# mega_shield_despair.net
KiCad netlist of a schematic drawn in EAGLE
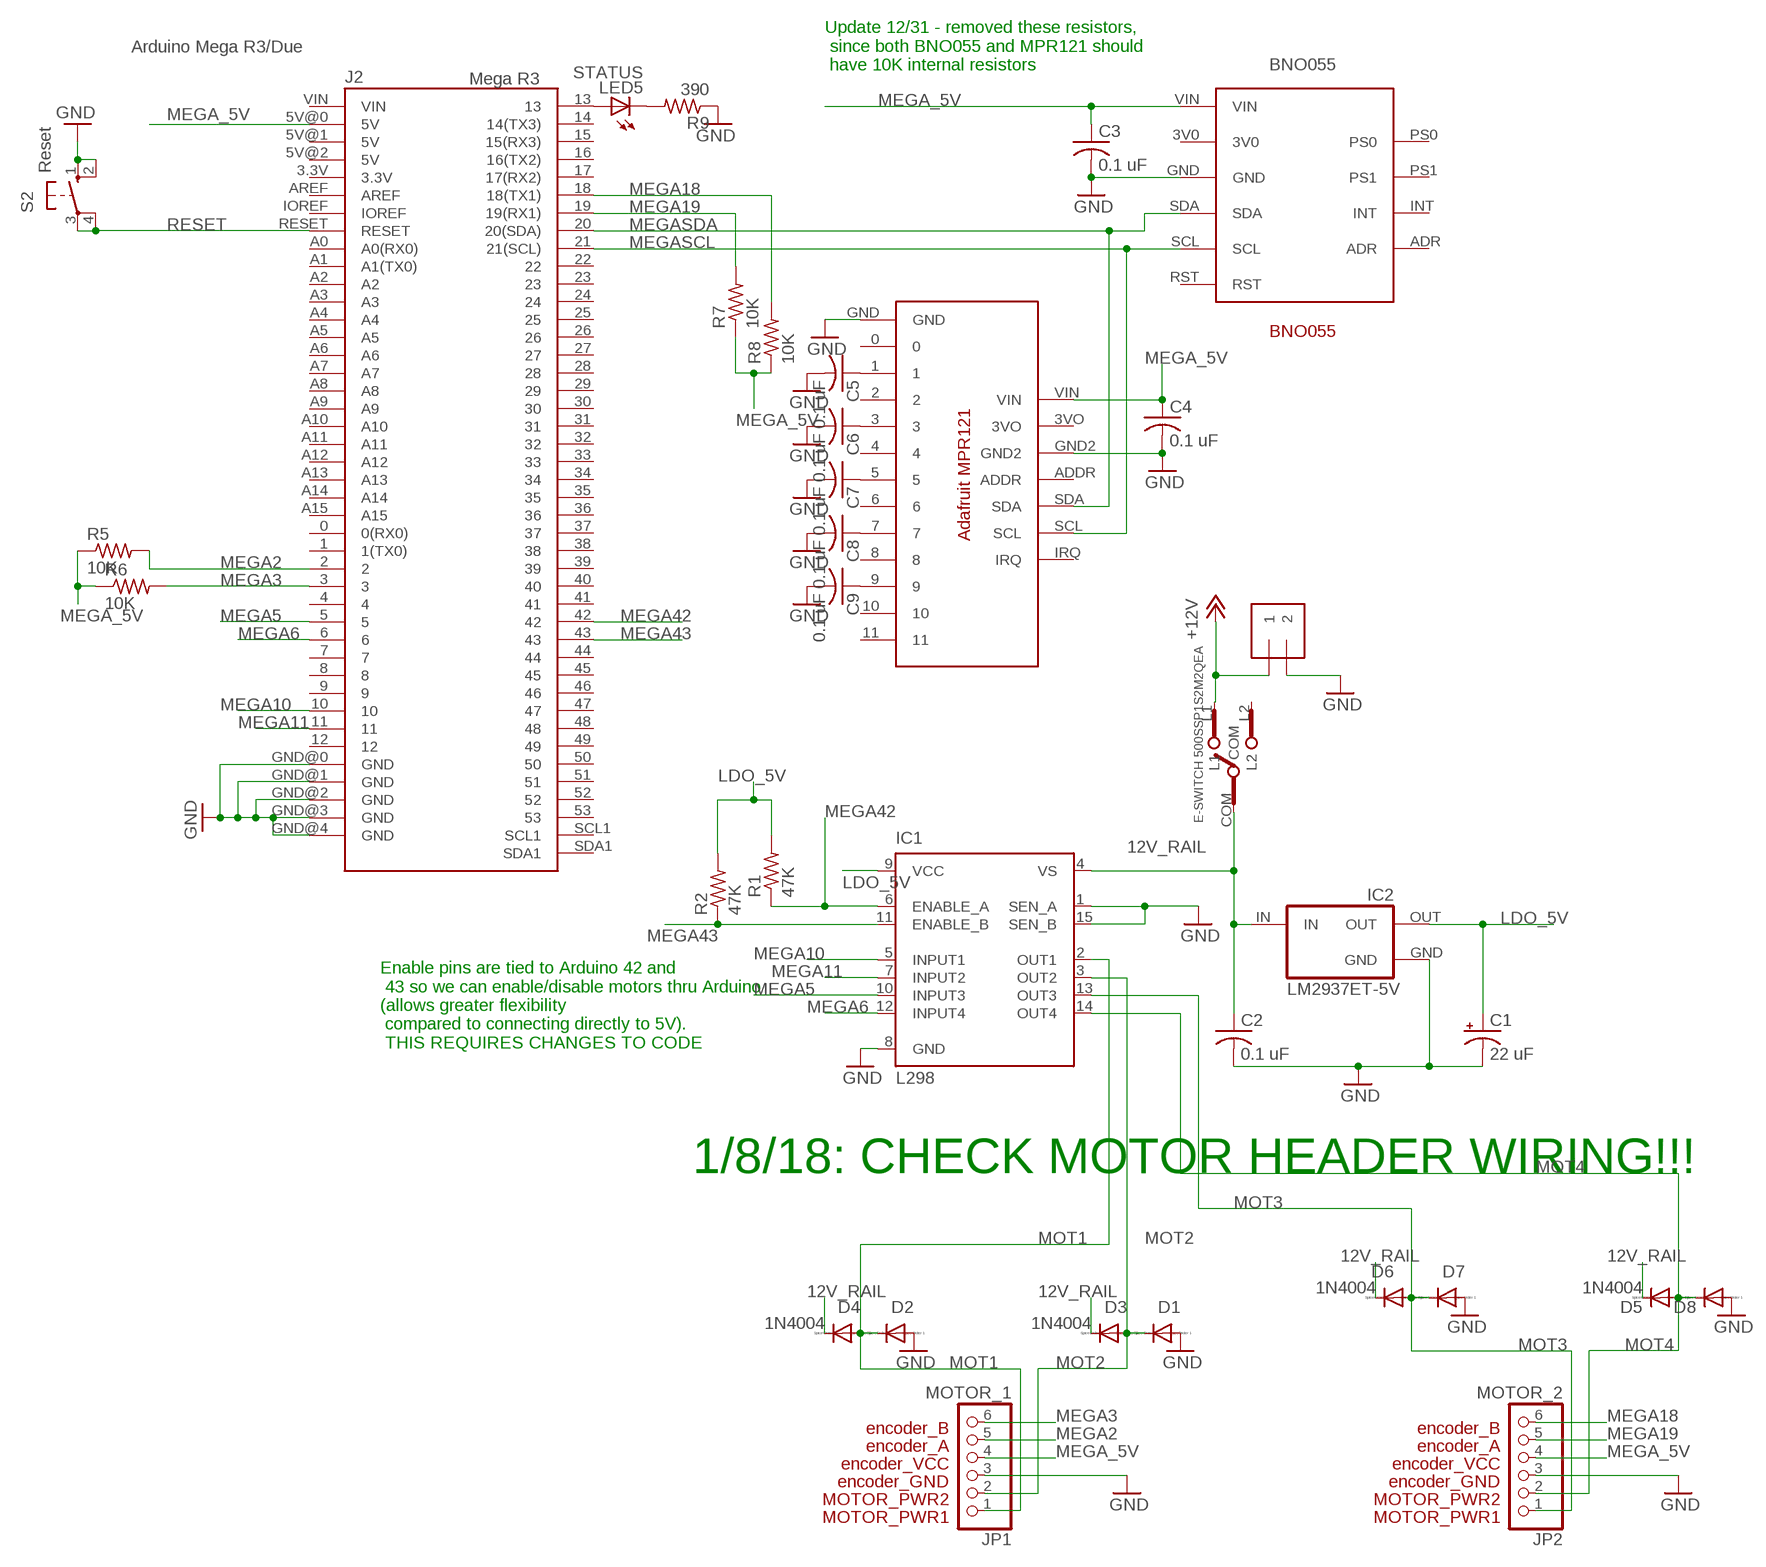
[diagram p0: schematic, sheet 1]

(export (version "E")
  (design (tool "Eeschema 10.0.6"))
  (components
    (comp (ref "12V_IN")
      (value "1X2-3.5MM")
      (footprint "eagle-import:1X2-3.5MM")
      (libsource (lib "eagle-import") (part "1X2-3.5MM"))
    )
    (comp (ref "BNO055")
      (value "BNO055")
      (footprint "eagle-import:BNO055")
      (libsource (lib "eagle-import") (part "BNO055"))
    )
    (comp (ref "C1")
      (value "22 uF")
      (footprint "eagle-import:B45181A")
      (libsource (lib "eagle-import") (part "CPOL-USB45181A"))
    )
    (comp (ref "C2")
      (value "0.1 uF")
      (footprint "eagle-import:C025-050X050")
      (libsource (lib "eagle-import") (part "C-US025-050X050"))
    )
    (comp (ref "C3")
      (value "0.1 uF")
      (footprint "eagle-import:C025-050X050")
      (libsource (lib "eagle-import") (part "C-US025-050X050"))
    )
    (comp (ref "C4")
      (value "0.1 uF")
      (footprint "eagle-import:C025-050X050")
      (libsource (lib "eagle-import") (part "C-US025-050X050"))
    )
    (comp (ref "C5")
      (value "0.1 uF")
      (footprint "eagle-import:C025-050X050")
      (libsource (lib "eagle-import") (part "C-US025-050X050"))
    )
    (comp (ref "C6")
      (value "0.1 uF")
      (footprint "eagle-import:C025-050X050")
      (libsource (lib "eagle-import") (part "C-US025-050X050"))
    )
    (comp (ref "C7")
      (value "0.1 uF")
      (footprint "eagle-import:C025-050X050")
      (libsource (lib "eagle-import") (part "C-US025-050X050"))
    )
    (comp (ref "C8")
      (value "0.1 uF")
      (footprint "eagle-import:C025-050X050")
      (libsource (lib "eagle-import") (part "C-US025-050X050"))
    )
    (comp (ref "C9")
      (value "0.1 uF")
      (footprint "eagle-import:C025-050X050")
      (libsource (lib "eagle-import") (part "C-US025-050X050"))
    )
    (comp (ref "D1")
      (value "1N4004")
      (footprint "eagle-import:DO41-10")
      (libsource (lib "eagle-import") (part "1N4004"))
    )
    (comp (ref "D2")
      (value "1N4004")
      (footprint "eagle-import:DO41-10")
      (libsource (lib "eagle-import") (part "1N4004"))
    )
    (comp (ref "D3")
      (value "1N4004")
      (footprint "eagle-import:DO41-10")
      (libsource (lib "eagle-import") (part "1N4004"))
    )
    (comp (ref "D4")
      (value "1N4004")
      (footprint "eagle-import:DO41-10")
      (libsource (lib "eagle-import") (part "1N4004"))
    )
    (comp (ref "D5")
      (value "1N4004")
      (footprint "eagle-import:DO41-10")
      (libsource (lib "eagle-import") (part "1N4004"))
    )
    (comp (ref "D6")
      (value "1N4004")
      (footprint "eagle-import:DO41-10")
      (libsource (lib "eagle-import") (part "1N4004"))
    )
    (comp (ref "D7")
      (value "1N4004")
      (footprint "eagle-import:DO41-10")
      (libsource (lib "eagle-import") (part "1N4004"))
    )
    (comp (ref "D8")
      (value "1N4004")
      (footprint "eagle-import:DO41-10")
      (libsource (lib "eagle-import") (part "1N4004"))
    )
    (comp (ref "IC1")
      (value "L298")
      (footprint "eagle-import:MULTIWATT-15")
      (fields (field (name "MPN") "L298N"))
      (libsource (lib "eagle-import") (part "L298"))
    )
    (comp (ref "IC2")
      (value "LM2937ET-5V")
      (footprint "eagle-import:TO220(V)")
      (libsource (lib "eagle-import") (part "LM2937ET-5,0"))
    )
    (comp (ref "J2")
      (value "Mega R3")
      (footprint "eagle-import:ARDUINO_MEGA")
      (libsource (lib "eagle-import") (part "ARDUINO-MEGAFULL"))
    )
    (comp (ref "JP1")
      (value "MOTOR_1")
      (footprint "eagle-import:1X06")
      (libsource (lib "eagle-import") (part "PINHD-1X6"))
    )
    (comp (ref "JP2")
      (value "MOTOR_2")
      (footprint "eagle-import:1X06")
      (libsource (lib "eagle-import") (part "PINHD-1X6"))
    )
    (comp (ref "LED5")
      (value "STATUS")
      (footprint "eagle-import:LED3MM")
      (libsource (lib "eagle-import") (part "LED3MM"))
    )
    (comp (ref "MPR121")
      (value "ADA_MPR121")
      (footprint "eagle-import:ADA_MPR121")
      (libsource (lib "eagle-import") (part "ADA_MPR121"))
    )
    (comp (ref "R1")
      (value "47K")
      (footprint "eagle-import:0207_10")
      (libsource (lib "eagle-import") (part "R-US_0207/10"))
    )
    (comp (ref "R2")
      (value "47K")
      (footprint "eagle-import:0207_10")
      (libsource (lib "eagle-import") (part "R-US_0207/10"))
    )
    (comp (ref "R5")
      (value "10K")
      (footprint "eagle-import:0207_10")
      (libsource (lib "eagle-import") (part "R-US_0207/10"))
    )
    (comp (ref "R6")
      (value "10K")
      (footprint "eagle-import:0207_10")
      (libsource (lib "eagle-import") (part "R-US_0207/10"))
    )
    (comp (ref "R7")
      (value "10K")
      (footprint "eagle-import:0207_10")
      (libsource (lib "eagle-import") (part "R-US_0207/10"))
    )
    (comp (ref "R8")
      (value "10K")
      (footprint "eagle-import:0207_10")
      (libsource (lib "eagle-import") (part "R-US_0207/10"))
    )
    (comp (ref "R9")
      (value "390")
      (footprint "eagle-import:0207_10")
      (libsource (lib "eagle-import") (part "R-US_0207/10"))
    )
    (comp (ref "S2")
      (value "Reset")
      (footprint "eagle-import:B3F-10XX")
      (fields (field (name "MPN") "B3F-1000"))
      (libsource (lib "eagle-import") (part "10-XX"))
    )
    (comp (ref "SLIDE_SW")
      (value "E-SWITCH_500SSP1S2M2QEA")
      (footprint "eagle-import:E-SWITCH_500SSP1S2M2QEA")
      (libsource (lib "eagle-import") (part "E-SWITCH_500SSP1S2M2QEA"))
    )
  )
  (nets
    (net (code "1") (name "+12V") (class "Default")
      (node (ref "12V_IN") (pin "1") (pinfunction "1_1") (pintype "passive"))
      (node (ref "SLIDE_SW") (pin "L1") (pinfunction "L1_L1") (pintype "bidirectional"))
    )
    (net (code "2") (name "/12V_RAIL") (class "Default")
      (node (ref "C2") (pin "1") (pinfunction "1_1") (pintype "passive"))
      (node (ref "D3") (pin "C") (pinfunction "C_C") (pintype "passive"))
      (node (ref "D4") (pin "C") (pinfunction "C_C") (pintype "passive"))
      (node (ref "D5") (pin "C") (pinfunction "C_C") (pintype "passive"))
      (node (ref "D6") (pin "C") (pinfunction "C_C") (pintype "passive"))
      (node (ref "IC1") (pin "4") (pinfunction "VS_4") (pintype "power_in"))
      (node (ref "IC2") (pin "IN") (pinfunction "IN_IN") (pintype "input"))
      (node (ref "SLIDE_SW") (pin "COM") (pinfunction "COM_COM") (pintype "bidirectional"))
    )
    (net (code "3") (name "/LDO_5V") (class "Default")
      (node (ref "C1") (pin "+") (pinfunction "+_+") (pintype "passive"))
      (node (ref "IC1") (pin "9") (pinfunction "VCC_9") (pintype "power_in"))
      (node (ref "IC2") (pin "OUT") (pinfunction "OUT_OUT") (pintype "output"))
      (node (ref "R1") (pin "2") (pinfunction "2_2") (pintype "passive"))
      (node (ref "R2") (pin "2") (pinfunction "2_2") (pintype "passive"))
    )
    (net (code "4") (name "/MEGA2") (class "Default")
      (node (ref "J2") (pin "2") (pinfunction "2_2") (pintype "bidirectional"))
      (node (ref "JP1") (pin "5") (pinfunction "5_5") (pintype "passive"))
      (node (ref "R5") (pin "2") (pinfunction "2_2") (pintype "passive"))
    )
    (net (code "5") (name "/MEGA3") (class "Default")
      (node (ref "J2") (pin "3") (pinfunction "3_3") (pintype "bidirectional"))
      (node (ref "JP1") (pin "6") (pinfunction "6_6") (pintype "passive"))
      (node (ref "R6") (pin "2") (pinfunction "2_2") (pintype "passive"))
    )
    (net (code "6") (name "/MEGA5") (class "Default")
      (node (ref "IC1") (pin "10") (pinfunction "INPUT3_10") (pintype "input"))
      (node (ref "J2") (pin "5") (pinfunction "5_5") (pintype "bidirectional"))
    )
    (net (code "7") (name "/MEGA6") (class "Default")
      (node (ref "IC1") (pin "12") (pinfunction "INPUT4_12") (pintype "input"))
      (node (ref "J2") (pin "6") (pinfunction "6_6") (pintype "bidirectional"))
    )
    (net (code "8") (name "/MEGA10") (class "Default")
      (node (ref "IC1") (pin "5") (pinfunction "INPUT1_5") (pintype "input"))
      (node (ref "J2") (pin "10") (pinfunction "10_10") (pintype "bidirectional"))
    )
    (net (code "9") (name "/MEGA11") (class "Default")
      (node (ref "IC1") (pin "7") (pinfunction "INPUT2_7") (pintype "input"))
      (node (ref "J2") (pin "11") (pinfunction "11_11") (pintype "bidirectional"))
    )
    (net (code "10") (name "/MEGA18") (class "Default")
      (node (ref "J2") (pin "18") (pinfunction "18(TX1)_18") (pintype "bidirectional"))
      (node (ref "JP2") (pin "6") (pinfunction "6_6") (pintype "passive"))
      (node (ref "R8") (pin "2") (pinfunction "2_2") (pintype "passive"))
    )
    (net (code "11") (name "/MEGA19") (class "Default")
      (node (ref "J2") (pin "19") (pinfunction "19(RX1)_19") (pintype "bidirectional"))
      (node (ref "JP2") (pin "5") (pinfunction "5_5") (pintype "passive"))
      (node (ref "R7") (pin "2") (pinfunction "2_2") (pintype "passive"))
    )
    (net (code "12") (name "/MEGA42") (class "Default")
      (node (ref "IC1") (pin "6") (pinfunction "ENABLE_A_6") (pintype "input"))
      (node (ref "J2") (pin "42") (pinfunction "42_42") (pintype "bidirectional"))
      (node (ref "R1") (pin "1") (pinfunction "1_1") (pintype "passive"))
    )
    (net (code "13") (name "/MEGA43") (class "Default")
      (node (ref "IC1") (pin "11") (pinfunction "ENABLE_B_11") (pintype "input"))
      (node (ref "J2") (pin "43") (pinfunction "43_43") (pintype "bidirectional"))
      (node (ref "R2") (pin "1") (pinfunction "1_1") (pintype "passive"))
    )
    (net (code "14") (name "/MEGASCL") (class "Default")
      (node (ref "BNO055") (pin "SCL") (pinfunction "SCL_SCL") (pintype "bidirectional"))
      (node (ref "J2") (pin "21") (pinfunction "21(SCL)_21") (pintype "bidirectional"))
      (node (ref "MPR121") (pin "SCL") (pinfunction "SCL_SCL") (pintype "bidirectional"))
    )
    (net (code "15") (name "/MEGASDA") (class "Default")
      (node (ref "BNO055") (pin "SDA") (pinfunction "SDA_SDA") (pintype "bidirectional"))
      (node (ref "J2") (pin "20") (pinfunction "20(SDA)_20") (pintype "bidirectional"))
      (node (ref "MPR121") (pin "SDA") (pinfunction "SDA_SDA") (pintype "bidirectional"))
    )
    (net (code "16") (name "/MEGA_5V") (class "Default")
      (node (ref "BNO055") (pin "VIN") (pinfunction "VIN_VIN") (pintype "bidirectional"))
      (node (ref "C3") (pin "1") (pinfunction "1_1") (pintype "passive"))
      (node (ref "C4") (pin "1") (pinfunction "1_1") (pintype "passive"))
      (node (ref "J2") (pin "5V@0") (pinfunction "5V_5V@0") (pintype "bidirectional"))
      (node (ref "JP1") (pin "4") (pinfunction "4_4") (pintype "passive"))
      (node (ref "JP2") (pin "4") (pinfunction "4_4") (pintype "passive"))
      (node (ref "MPR121") (pin "VIN") (pinfunction "VIN_VIN") (pintype "bidirectional"))
      (node (ref "R5") (pin "1") (pinfunction "1_1") (pintype "passive"))
      (node (ref "R6") (pin "1") (pinfunction "1_1") (pintype "passive"))
      (node (ref "R7") (pin "1") (pinfunction "1_1") (pintype "passive"))
      (node (ref "R8") (pin "1") (pinfunction "1_1") (pintype "passive"))
    )
    (net (code "17") (name "/MOT1") (class "Default")
      (node (ref "D2") (pin "C") (pinfunction "C_C") (pintype "passive"))
      (node (ref "D4") (pin "A") (pinfunction "A_A") (pintype "passive"))
      (node (ref "IC1") (pin "2") (pinfunction "OUT1_2") (pintype "output"))
      (node (ref "JP1") (pin "1") (pinfunction "1_1") (pintype "passive"))
    )
    (net (code "18") (name "/MOT2") (class "Default")
      (node (ref "D1") (pin "C") (pinfunction "C_C") (pintype "passive"))
      (node (ref "D3") (pin "A") (pinfunction "A_A") (pintype "passive"))
      (node (ref "IC1") (pin "3") (pinfunction "OUT2_3") (pintype "output"))
      (node (ref "JP1") (pin "2") (pinfunction "2_2") (pintype "passive"))
    )
    (net (code "19") (name "/MOT3") (class "Default")
      (node (ref "D6") (pin "A") (pinfunction "A_A") (pintype "passive"))
      (node (ref "D7") (pin "C") (pinfunction "C_C") (pintype "passive"))
      (node (ref "IC1") (pin "13") (pinfunction "OUT3_13") (pintype "output"))
      (node (ref "JP2") (pin "1") (pinfunction "1_1") (pintype "passive"))
    )
    (net (code "20") (name "/MOT4") (class "Default")
      (node (ref "D5") (pin "A") (pinfunction "A_A") (pintype "passive"))
      (node (ref "D8") (pin "C") (pinfunction "C_C") (pintype "passive"))
      (node (ref "IC1") (pin "14") (pinfunction "OUT4_14") (pintype "output"))
      (node (ref "JP2") (pin "2") (pinfunction "2_2") (pintype "passive"))
    )
    (net (code "21") (name "/RESET") (class "Default")
      (node (ref "J2") (pin "RESET") (pinfunction "RESET_RESET") (pintype "bidirectional"))
      (node (ref "S2") (pin "3") (pinfunction "P_3") (pintype "passive"))
      (node (ref "S2") (pin "4") (pinfunction "P1_4") (pintype "passive"))
    )
    (net (code "22") (name "GND") (class "Default")
      (node (ref "12V_IN") (pin "2") (pinfunction "2_2") (pintype "passive"))
      (node (ref "BNO055") (pin "GND") (pinfunction "GND_GND") (pintype "bidirectional"))
      (node (ref "C1") (pin "-") (pinfunction "-_-") (pintype "passive"))
      (node (ref "C2") (pin "2") (pinfunction "2_2") (pintype "passive"))
      (node (ref "C3") (pin "2") (pinfunction "2_2") (pintype "passive"))
      (node (ref "C4") (pin "2") (pinfunction "2_2") (pintype "passive"))
      (node (ref "C5") (pin "2") (pinfunction "2_2") (pintype "passive"))
      (node (ref "C6") (pin "2") (pinfunction "2_2") (pintype "passive"))
      (node (ref "C7") (pin "2") (pinfunction "2_2") (pintype "passive"))
      (node (ref "C8") (pin "2") (pinfunction "2_2") (pintype "passive"))
      (node (ref "C9") (pin "2") (pinfunction "2_2") (pintype "passive"))
      (node (ref "D1") (pin "A") (pinfunction "A_A") (pintype "passive"))
      (node (ref "D2") (pin "A") (pinfunction "A_A") (pintype "passive"))
      (node (ref "D7") (pin "A") (pinfunction "A_A") (pintype "passive"))
      (node (ref "D8") (pin "A") (pinfunction "A_A") (pintype "passive"))
      (node (ref "IC1") (pin "1") (pinfunction "SEN_A_1") (pintype "input"))
      (node (ref "IC1") (pin "15") (pinfunction "SEN_B_15") (pintype "input"))
      (node (ref "IC1") (pin "8") (pinfunction "GND_8") (pintype "power_in"))
      (node (ref "IC2") (pin "GND") (pinfunction "GND_GND") (pintype "power_in"))
      (node (ref "J2") (pin "GND@0") (pinfunction "GND_GND@0") (pintype "bidirectional"))
      (node (ref "J2") (pin "GND@1") (pinfunction "GND_GND@1") (pintype "bidirectional"))
      (node (ref "J2") (pin "GND@2") (pinfunction "GND_GND@2") (pintype "bidirectional"))
      (node (ref "J2") (pin "GND@3") (pinfunction "GND_GND@3") (pintype "bidirectional"))
      (node (ref "J2") (pin "GND@4") (pinfunction "GND_GND@4") (pintype "bidirectional"))
      (node (ref "JP1") (pin "3") (pinfunction "3_3") (pintype "passive"))
      (node (ref "JP2") (pin "3") (pinfunction "3_3") (pintype "passive"))
      (node (ref "MPR121") (pin "GND") (pinfunction "GND_GND") (pintype "bidirectional"))
      (node (ref "MPR121") (pin "GND2") (pinfunction "GND2_GND2") (pintype "bidirectional"))
      (node (ref "R9") (pin "1") (pinfunction "1_1") (pintype "passive"))
      (node (ref "S2") (pin "1") (pinfunction "S_1") (pintype "passive"))
      (node (ref "S2") (pin "2") (pinfunction "S1_2") (pintype "passive"))
    )
    (net (code "23") (name "Net-(C5-Pad1)") (class "Default")
      (node (ref "C5") (pin "1") (pinfunction "1_1") (pintype "passive"))
      (node (ref "MPR121") (pin "1") (pinfunction "1_1") (pintype "bidirectional"))
    )
    (net (code "24") (name "Net-(C6-Pad1)") (class "Default")
      (node (ref "C6") (pin "1") (pinfunction "1_1") (pintype "passive"))
      (node (ref "MPR121") (pin "3") (pinfunction "3_3") (pintype "bidirectional"))
    )
    (net (code "25") (name "Net-(C7-Pad1)") (class "Default")
      (node (ref "C7") (pin "1") (pinfunction "1_1") (pintype "passive"))
      (node (ref "MPR121") (pin "5") (pinfunction "5_5") (pintype "bidirectional"))
    )
    (net (code "26") (name "Net-(C8-Pad1)") (class "Default")
      (node (ref "C8") (pin "1") (pinfunction "1_1") (pintype "passive"))
      (node (ref "MPR121") (pin "7") (pinfunction "7_7") (pintype "bidirectional"))
    )
    (net (code "27") (name "Net-(C9-Pad1)") (class "Default")
      (node (ref "C9") (pin "1") (pinfunction "1_1") (pintype "passive"))
      (node (ref "MPR121") (pin "9") (pinfunction "9_9") (pintype "bidirectional"))
    )
    (net (code "28") (name "Net-(J2-Pad13)") (class "Default")
      (node (ref "J2") (pin "13") (pinfunction "13_13") (pintype "bidirectional"))
      (node (ref "LED5") (pin "A") (pinfunction "A_A") (pintype "passive"))
    )
    (net (code "29") (name "Net-(LED5-C)") (class "Default")
      (node (ref "LED5") (pin "K") (pinfunction "C_K") (pintype "passive"))
      (node (ref "R9") (pin "2") (pinfunction "2_2") (pintype "passive"))
    )
    (net (code "30") (name "unconnected-(BNO055-Pad3V0)") (class "Default")
      (node (ref "BNO055") (pin "3V0") (pinfunction "3V0_3V0") (pintype "bidirectional"))
    )
    (net (code "31") (name "unconnected-(BNO055-PadADR)") (class "Default")
      (node (ref "BNO055") (pin "ADR") (pinfunction "ADR_ADR") (pintype "bidirectional"))
    )
    (net (code "32") (name "unconnected-(BNO055-PadINT)") (class "Default")
      (node (ref "BNO055") (pin "INT") (pinfunction "INT_INT") (pintype "bidirectional"))
    )
    (net (code "33") (name "unconnected-(BNO055-PadPS0)") (class "Default")
      (node (ref "BNO055") (pin "PS0") (pinfunction "PS0_PS0") (pintype "bidirectional"))
    )
    (net (code "34") (name "unconnected-(BNO055-PadPS1)") (class "Default")
      (node (ref "BNO055") (pin "PS1") (pinfunction "PS1_PS1") (pintype "bidirectional"))
    )
    (net (code "35") (name "unconnected-(BNO055-PadRST)") (class "Default")
      (node (ref "BNO055") (pin "RST") (pinfunction "RST_RST") (pintype "bidirectional"))
    )
    (net (code "36") (name "unconnected-(J2-0(RX0)-Pad0)") (class "Default")
      (node (ref "J2") (pin "0") (pinfunction "0(RX0)_0") (pintype "bidirectional"))
    )
    (net (code "37") (name "unconnected-(J2-1(TX0)-Pad1)") (class "Default")
      (node (ref "J2") (pin "1") (pinfunction "1(TX0)_1") (pintype "bidirectional"))
    )
    (net (code "38") (name "unconnected-(J2-5V-Pad5V@1)") (class "Default")
      (node (ref "J2") (pin "5V@1") (pinfunction "5V_5V@1") (pintype "bidirectional"))
    )
    (net (code "39") (name "unconnected-(J2-5V-Pad5V@2)") (class "Default")
      (node (ref "J2") (pin "5V@2") (pinfunction "5V_5V@2") (pintype "bidirectional"))
    )
    (net (code "40") (name "unconnected-(J2-14(TX3)-Pad14)") (class "Default")
      (node (ref "J2") (pin "14") (pinfunction "14(TX3)_14") (pintype "bidirectional"))
    )
    (net (code "41") (name "unconnected-(J2-15(RX3)-Pad15)") (class "Default")
      (node (ref "J2") (pin "15") (pinfunction "15(RX3)_15") (pintype "bidirectional"))
    )
    (net (code "42") (name "unconnected-(J2-16(TX2)-Pad16)") (class "Default")
      (node (ref "J2") (pin "16") (pinfunction "16(TX2)_16") (pintype "bidirectional"))
    )
    (net (code "43") (name "unconnected-(J2-17(RX2)-Pad17)") (class "Default")
      (node (ref "J2") (pin "17") (pinfunction "17(RX2)_17") (pintype "bidirectional"))
    )
    (net (code "44") (name "unconnected-(J2-A0(RX0)-PadA0)") (class "Default")
      (node (ref "J2") (pin "A0") (pinfunction "A0(RX0)_A0") (pintype "bidirectional"))
    )
    (net (code "45") (name "unconnected-(J2-A1(TX0)-PadA1)") (class "Default")
      (node (ref "J2") (pin "A1") (pinfunction "A1(TX0)_A1") (pintype "bidirectional"))
    )
    (net (code "46") (name "unconnected-(J2-Pad3.3V)") (class "Default")
      (node (ref "J2") (pin "3.3V") (pinfunction "3.3V_3.3V") (pintype "bidirectional"))
    )
    (net (code "47") (name "unconnected-(J2-Pad4)") (class "Default")
      (node (ref "J2") (pin "4") (pinfunction "4_4") (pintype "bidirectional"))
    )
    (net (code "48") (name "unconnected-(J2-Pad7)") (class "Default")
      (node (ref "J2") (pin "7") (pinfunction "7_7") (pintype "bidirectional"))
    )
    (net (code "49") (name "unconnected-(J2-Pad8)") (class "Default")
      (node (ref "J2") (pin "8") (pinfunction "8_8") (pintype "bidirectional"))
    )
    (net (code "50") (name "unconnected-(J2-Pad9)") (class "Default")
      (node (ref "J2") (pin "9") (pinfunction "9_9") (pintype "bidirectional"))
    )
    (net (code "51") (name "unconnected-(J2-Pad12)") (class "Default")
      (node (ref "J2") (pin "12") (pinfunction "12_12") (pintype "bidirectional"))
    )
    (net (code "52") (name "unconnected-(J2-Pad22)") (class "Default")
      (node (ref "J2") (pin "22") (pinfunction "22_22") (pintype "bidirectional"))
    )
    (net (code "53") (name "unconnected-(J2-Pad23)") (class "Default")
      (node (ref "J2") (pin "23") (pinfunction "23_23") (pintype "bidirectional"))
    )
    (net (code "54") (name "unconnected-(J2-Pad24)") (class "Default")
      (node (ref "J2") (pin "24") (pinfunction "24_24") (pintype "bidirectional"))
    )
    (net (code "55") (name "unconnected-(J2-Pad25)") (class "Default")
      (node (ref "J2") (pin "25") (pinfunction "25_25") (pintype "bidirectional"))
    )
    (net (code "56") (name "unconnected-(J2-Pad26)") (class "Default")
      (node (ref "J2") (pin "26") (pinfunction "26_26") (pintype "bidirectional"))
    )
    (net (code "57") (name "unconnected-(J2-Pad27)") (class "Default")
      (node (ref "J2") (pin "27") (pinfunction "27_27") (pintype "bidirectional"))
    )
    (net (code "58") (name "unconnected-(J2-Pad28)") (class "Default")
      (node (ref "J2") (pin "28") (pinfunction "28_28") (pintype "bidirectional"))
    )
    (net (code "59") (name "unconnected-(J2-Pad29)") (class "Default")
      (node (ref "J2") (pin "29") (pinfunction "29_29") (pintype "bidirectional"))
    )
    (net (code "60") (name "unconnected-(J2-Pad30)") (class "Default")
      (node (ref "J2") (pin "30") (pinfunction "30_30") (pintype "bidirectional"))
    )
    (net (code "61") (name "unconnected-(J2-Pad31)") (class "Default")
      (node (ref "J2") (pin "31") (pinfunction "31_31") (pintype "bidirectional"))
    )
    (net (code "62") (name "unconnected-(J2-Pad32)") (class "Default")
      (node (ref "J2") (pin "32") (pinfunction "32_32") (pintype "bidirectional"))
    )
    (net (code "63") (name "unconnected-(J2-Pad33)") (class "Default")
      (node (ref "J2") (pin "33") (pinfunction "33_33") (pintype "bidirectional"))
    )
    (net (code "64") (name "unconnected-(J2-Pad34)") (class "Default")
      (node (ref "J2") (pin "34") (pinfunction "34_34") (pintype "bidirectional"))
    )
    (net (code "65") (name "unconnected-(J2-Pad35)") (class "Default")
      (node (ref "J2") (pin "35") (pinfunction "35_35") (pintype "bidirectional"))
    )
    (net (code "66") (name "unconnected-(J2-Pad36)") (class "Default")
      (node (ref "J2") (pin "36") (pinfunction "36_36") (pintype "bidirectional"))
    )
    (net (code "67") (name "unconnected-(J2-Pad37)") (class "Default")
      (node (ref "J2") (pin "37") (pinfunction "37_37") (pintype "bidirectional"))
    )
    (net (code "68") (name "unconnected-(J2-Pad38)") (class "Default")
      (node (ref "J2") (pin "38") (pinfunction "38_38") (pintype "bidirectional"))
    )
    (net (code "69") (name "unconnected-(J2-Pad39)") (class "Default")
      (node (ref "J2") (pin "39") (pinfunction "39_39") (pintype "bidirectional"))
    )
    (net (code "70") (name "unconnected-(J2-Pad40)") (class "Default")
      (node (ref "J2") (pin "40") (pinfunction "40_40") (pintype "bidirectional"))
    )
    (net (code "71") (name "unconnected-(J2-Pad41)") (class "Default")
      (node (ref "J2") (pin "41") (pinfunction "41_41") (pintype "bidirectional"))
    )
    (net (code "72") (name "unconnected-(J2-Pad44)") (class "Default")
      (node (ref "J2") (pin "44") (pinfunction "44_44") (pintype "bidirectional"))
    )
    (net (code "73") (name "unconnected-(J2-Pad45)") (class "Default")
      (node (ref "J2") (pin "45") (pinfunction "45_45") (pintype "bidirectional"))
    )
    (net (code "74") (name "unconnected-(J2-Pad46)") (class "Default")
      (node (ref "J2") (pin "46") (pinfunction "46_46") (pintype "bidirectional"))
    )
    (net (code "75") (name "unconnected-(J2-Pad47)") (class "Default")
      (node (ref "J2") (pin "47") (pinfunction "47_47") (pintype "bidirectional"))
    )
    (net (code "76") (name "unconnected-(J2-Pad48)") (class "Default")
      (node (ref "J2") (pin "48") (pinfunction "48_48") (pintype "bidirectional"))
    )
    (net (code "77") (name "unconnected-(J2-Pad49)") (class "Default")
      (node (ref "J2") (pin "49") (pinfunction "49_49") (pintype "bidirectional"))
    )
    (net (code "78") (name "unconnected-(J2-Pad50)") (class "Default")
      (node (ref "J2") (pin "50") (pinfunction "50_50") (pintype "bidirectional"))
    )
    (net (code "79") (name "unconnected-(J2-Pad51)") (class "Default")
      (node (ref "J2") (pin "51") (pinfunction "51_51") (pintype "bidirectional"))
    )
    (net (code "80") (name "unconnected-(J2-Pad52)") (class "Default")
      (node (ref "J2") (pin "52") (pinfunction "52_52") (pintype "bidirectional"))
    )
    (net (code "81") (name "unconnected-(J2-Pad53)") (class "Default")
      (node (ref "J2") (pin "53") (pinfunction "53_53") (pintype "bidirectional"))
    )
    (net (code "82") (name "unconnected-(J2-PadA2)") (class "Default")
      (node (ref "J2") (pin "A2") (pinfunction "A2_A2") (pintype "bidirectional"))
    )
    (net (code "83") (name "unconnected-(J2-PadA3)") (class "Default")
      (node (ref "J2") (pin "A3") (pinfunction "A3_A3") (pintype "bidirectional"))
    )
    (net (code "84") (name "unconnected-(J2-PadA4)") (class "Default")
      (node (ref "J2") (pin "A4") (pinfunction "A4_A4") (pintype "bidirectional"))
    )
    (net (code "85") (name "unconnected-(J2-PadA5)") (class "Default")
      (node (ref "J2") (pin "A5") (pinfunction "A5_A5") (pintype "bidirectional"))
    )
    (net (code "86") (name "unconnected-(J2-PadA6)") (class "Default")
      (node (ref "J2") (pin "A6") (pinfunction "A6_A6") (pintype "bidirectional"))
    )
    (net (code "87") (name "unconnected-(J2-PadA7)") (class "Default")
      (node (ref "J2") (pin "A7") (pinfunction "A7_A7") (pintype "bidirectional"))
    )
    (net (code "88") (name "unconnected-(J2-PadA8)") (class "Default")
      (node (ref "J2") (pin "A8") (pinfunction "A8_A8") (pintype "bidirectional"))
    )
    (net (code "89") (name "unconnected-(J2-PadA9)") (class "Default")
      (node (ref "J2") (pin "A9") (pinfunction "A9_A9") (pintype "bidirectional"))
    )
    (net (code "90") (name "unconnected-(J2-PadA10)") (class "Default")
      (node (ref "J2") (pin "A10") (pinfunction "A10_A10") (pintype "bidirectional"))
    )
    (net (code "91") (name "unconnected-(J2-PadA11)") (class "Default")
      (node (ref "J2") (pin "A11") (pinfunction "A11_A11") (pintype "bidirectional"))
    )
    (net (code "92") (name "unconnected-(J2-PadA12)") (class "Default")
      (node (ref "J2") (pin "A12") (pinfunction "A12_A12") (pintype "bidirectional"))
    )
    (net (code "93") (name "unconnected-(J2-PadA13)") (class "Default")
      (node (ref "J2") (pin "A13") (pinfunction "A13_A13") (pintype "bidirectional"))
    )
    (net (code "94") (name "unconnected-(J2-PadA14)") (class "Default")
      (node (ref "J2") (pin "A14") (pinfunction "A14_A14") (pintype "bidirectional"))
    )
    (net (code "95") (name "unconnected-(J2-PadA15)") (class "Default")
      (node (ref "J2") (pin "A15") (pinfunction "A15_A15") (pintype "bidirectional"))
    )
    (net (code "96") (name "unconnected-(J2-PadAREF)") (class "Default")
      (node (ref "J2") (pin "AREF") (pinfunction "AREF_AREF") (pintype "bidirectional"))
    )
    (net (code "97") (name "unconnected-(J2-PadIOREF)") (class "Default")
      (node (ref "J2") (pin "IOREF") (pinfunction "IOREF_IOREF") (pintype "bidirectional"))
    )
    (net (code "98") (name "unconnected-(J2-PadSCL1)") (class "Default")
      (node (ref "J2") (pin "SCL1") (pinfunction "SCL1_SCL1") (pintype "bidirectional"))
    )
    (net (code "99") (name "unconnected-(J2-PadSDA1)") (class "Default")
      (node (ref "J2") (pin "SDA1") (pinfunction "SDA1_SDA1") (pintype "bidirectional"))
    )
    (net (code "100") (name "unconnected-(J2-PadVIN)") (class "Default")
      (node (ref "J2") (pin "VIN") (pinfunction "VIN_VIN") (pintype "bidirectional"))
    )
    (net (code "101") (name "unconnected-(MPR121-Pad0)") (class "Default")
      (node (ref "MPR121") (pin "0") (pinfunction "0_0") (pintype "bidirectional"))
    )
    (net (code "102") (name "unconnected-(MPR121-Pad2)") (class "Default")
      (node (ref "MPR121") (pin "2") (pinfunction "2_2") (pintype "bidirectional"))
    )
    (net (code "103") (name "unconnected-(MPR121-Pad3VO)") (class "Default")
      (node (ref "MPR121") (pin "3VO") (pinfunction "3VO_3VO") (pintype "bidirectional"))
    )
    (net (code "104") (name "unconnected-(MPR121-Pad4)") (class "Default")
      (node (ref "MPR121") (pin "4") (pinfunction "4_4") (pintype "bidirectional"))
    )
    (net (code "105") (name "unconnected-(MPR121-Pad6)") (class "Default")
      (node (ref "MPR121") (pin "6") (pinfunction "6_6") (pintype "bidirectional"))
    )
    (net (code "106") (name "unconnected-(MPR121-Pad8)") (class "Default")
      (node (ref "MPR121") (pin "8") (pinfunction "8_8") (pintype "bidirectional"))
    )
    (net (code "107") (name "unconnected-(MPR121-Pad10)") (class "Default")
      (node (ref "MPR121") (pin "10") (pinfunction "10_10") (pintype "bidirectional"))
    )
    (net (code "108") (name "unconnected-(MPR121-Pad11)") (class "Default")
      (node (ref "MPR121") (pin "11") (pinfunction "11_11") (pintype "bidirectional"))
    )
    (net (code "109") (name "unconnected-(MPR121-PadADDR)") (class "Default")
      (node (ref "MPR121") (pin "ADDR") (pinfunction "ADDR_ADDR") (pintype "bidirectional"))
    )
    (net (code "110") (name "unconnected-(MPR121-PadIRQ)") (class "Default")
      (node (ref "MPR121") (pin "IRQ") (pinfunction "IRQ_IRQ") (pintype "bidirectional"))
    )
    (net (code "111") (name "unconnected-(SLIDE_SW-PadL2)") (class "Default")
      (node (ref "SLIDE_SW") (pin "L2") (pinfunction "L2_L2") (pintype "bidirectional"))
    )
  )
)
